# GB_Slave_2015.net
KiCad netlist of a schematic drawn in EAGLE
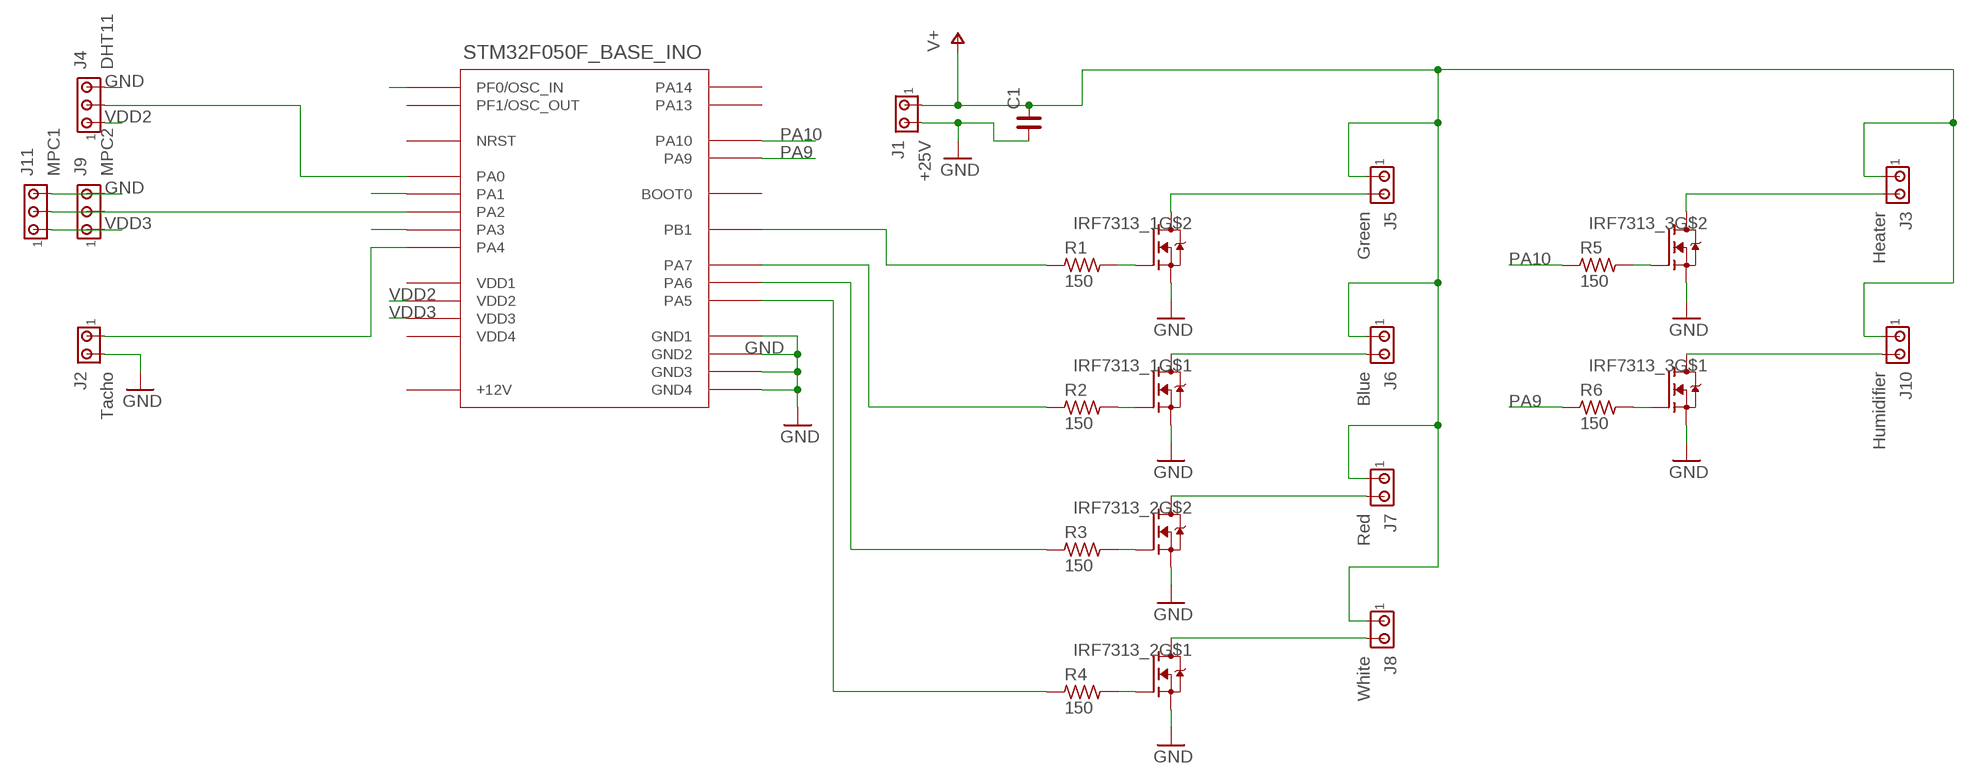
[diagram p0: schematic, sheet 1]

(export (version "E")
  (design (tool "Eeschema 10.0.6"))
  (components
    (comp (ref "C1")
      (value "C_0603")
      (footprint "eagle-import:C0603")
      (libsource (lib "eagle-import") (part "C_0603"))
    )
    (comp (ref "IRF7313_1")
      (value "IRF7313")
      (footprint "eagle-import:SO-8")
      (libsource (lib "eagle-import") (part "IRF7313"))
    )
    (comp (ref "IRF7313_2")
      (value "IRF7313")
      (footprint "eagle-import:SO-8")
      (libsource (lib "eagle-import") (part "IRF7313"))
    )
    (comp (ref "IRF7313_3")
      (value "IRF7313")
      (footprint "eagle-import:SO-8")
      (libsource (lib "eagle-import") (part "IRF7313"))
    )
    (comp (ref "J1")
      (value "+25V")
      (footprint "eagle-import:10X02MTA")
      (libsource (lib "eagle-import") (part "MTA02-100"))
    )
    (comp (ref "J2")
      (value "Tacho")
      (footprint "eagle-import:10X02MTA")
      (libsource (lib "eagle-import") (part "MTA02-100"))
    )
    (comp (ref "J3")
      (value "Heater")
      (footprint "eagle-import:10X02MTA")
      (libsource (lib "eagle-import") (part "MTA02-100"))
    )
    (comp (ref "J4")
      (value "DHT11")
      (footprint "eagle-import:10X03MTA")
      (libsource (lib "eagle-import") (part "MTA03-100"))
    )
    (comp (ref "J5")
      (value "Green")
      (footprint "eagle-import:10X02MTA")
      (libsource (lib "eagle-import") (part "MTA02-100"))
    )
    (comp (ref "J6")
      (value "Blue")
      (footprint "eagle-import:10X02MTA")
      (libsource (lib "eagle-import") (part "MTA02-100"))
    )
    (comp (ref "J7")
      (value "Red")
      (footprint "eagle-import:10X02MTA")
      (libsource (lib "eagle-import") (part "MTA02-100"))
    )
    (comp (ref "J8")
      (value "White")
      (footprint "eagle-import:10X02MTA")
      (libsource (lib "eagle-import") (part "MTA02-100"))
    )
    (comp (ref "J9")
      (value "MPC2")
      (footprint "eagle-import:10X03MTA")
      (libsource (lib "eagle-import") (part "MTA03-100"))
    )
    (comp (ref "J10")
      (value "Humidifier")
      (footprint "eagle-import:10X02MTA")
      (libsource (lib "eagle-import") (part "MTA02-100"))
    )
    (comp (ref "J11")
      (value "MPC1")
      (footprint "eagle-import:10X03MTA")
      (libsource (lib "eagle-import") (part "MTA03-100"))
    )
    (comp (ref "R1")
      (value "150")
      (footprint "eagle-import:R1206")
      (libsource (lib "eagle-import") (part "R_1206"))
    )
    (comp (ref "R2")
      (value "150")
      (footprint "eagle-import:R1206")
      (libsource (lib "eagle-import") (part "R_1206"))
    )
    (comp (ref "R3")
      (value "150")
      (footprint "eagle-import:R1206")
      (libsource (lib "eagle-import") (part "R_1206"))
    )
    (comp (ref "R4")
      (value "150")
      (footprint "eagle-import:R1206")
      (libsource (lib "eagle-import") (part "R_1206"))
    )
    (comp (ref "R5")
      (value "150")
      (footprint "eagle-import:R1206")
      (libsource (lib "eagle-import") (part "R_1206"))
    )
    (comp (ref "R6")
      (value "150")
      (footprint "eagle-import:R1206")
      (libsource (lib "eagle-import") (part "R_1206"))
    )
    (comp (ref "STM321")
      (value "STM32F050F_BASE_INO")
      (footprint "eagle-import:STM32_BASE_INO")
      (libsource (lib "eagle-import") (part "STM32F050F_BASE_INO"))
    )
  )
  (nets
    (net (code "1") (name "/PA9") (class "Default")
      (node (ref "R6") (pin "1") (pinfunction "1_1") (pintype "passive"))
      (node (ref "STM321") (pin "PA9") (pinfunction "PA9_PA9") (pintype "passive"))
    )
    (net (code "2") (name "/PA10") (class "Default")
      (node (ref "R5") (pin "1") (pinfunction "1_1") (pintype "passive"))
      (node (ref "STM321") (pin "PA10") (pinfunction "PA10_PA10") (pintype "passive"))
    )
    (net (code "3") (name "/VDD2") (class "Default")
      (node (ref "J4") (pin "1") (pinfunction "1_1") (pintype "passive"))
      (node (ref "STM321") (pin "VDD2") (pinfunction "VDD2_VDD2") (pintype "passive"))
    )
    (net (code "4") (name "/VDD3") (class "Default")
      (node (ref "J11") (pin "1") (pinfunction "1_1") (pintype "passive"))
      (node (ref "J9") (pin "1") (pinfunction "1_1") (pintype "passive"))
      (node (ref "STM321") (pin "VDD3") (pinfunction "VDD3_VDD3") (pintype "passive"))
    )
    (net (code "5") (name "GND") (class "Default")
      (node (ref "C1") (pin "1") (pinfunction "1_1") (pintype "passive"))
      (node (ref "IRF7313_1") (pin "1") (pinfunction "S_1") (pintype "passive"))
      (node (ref "IRF7313_1") (pin "3") (pinfunction "S_3") (pintype "passive"))
      (node (ref "IRF7313_2") (pin "1") (pinfunction "S_1") (pintype "passive"))
      (node (ref "IRF7313_2") (pin "3") (pinfunction "S_3") (pintype "passive"))
      (node (ref "IRF7313_3") (pin "1") (pinfunction "S_1") (pintype "passive"))
      (node (ref "IRF7313_3") (pin "3") (pinfunction "S_3") (pintype "passive"))
      (node (ref "J1") (pin "2") (pinfunction "2_2") (pintype "passive"))
      (node (ref "J11") (pin "3") (pinfunction "3_3") (pintype "passive"))
      (node (ref "J2") (pin "2") (pinfunction "2_2") (pintype "passive"))
      (node (ref "J4") (pin "3") (pinfunction "3_3") (pintype "passive"))
      (node (ref "J9") (pin "3") (pinfunction "3_3") (pintype "passive"))
      (node (ref "STM321") (pin "GND1") (pinfunction "GND1_GND1") (pintype "passive"))
      (node (ref "STM321") (pin "GND2") (pinfunction "GND2_GND2") (pintype "passive"))
      (node (ref "STM321") (pin "GND3") (pinfunction "GND3_GND3") (pintype "passive"))
      (node (ref "STM321") (pin "GND4") (pinfunction "GND4_GND4") (pintype "passive"))
    )
    (net (code "6") (name "Net-(IRF7313_1A-D-Pad7)") (class "Default")
      (node (ref "IRF7313_1") (pin "7") (pinfunction "D_7") (pintype "passive"))
      (node (ref "IRF7313_1") (pin "8") (pinfunction "D_8") (pintype "passive"))
      (node (ref "J6") (pin "2") (pinfunction "2_2") (pintype "passive"))
    )
    (net (code "7") (name "Net-(IRF7313_1A-G)") (class "Default")
      (node (ref "IRF7313_1") (pin "2") (pinfunction "G_2") (pintype "passive"))
      (node (ref "R2") (pin "2") (pinfunction "2_2") (pintype "passive"))
    )
    (net (code "8") (name "Net-(IRF7313_1B-D-Pad5)") (class "Default")
      (node (ref "IRF7313_1") (pin "5") (pinfunction "D_5") (pintype "passive"))
      (node (ref "IRF7313_1") (pin "6") (pinfunction "D_6") (pintype "passive"))
      (node (ref "J5") (pin "2") (pinfunction "2_2") (pintype "passive"))
    )
    (net (code "9") (name "Net-(IRF7313_1B-G)") (class "Default")
      (node (ref "IRF7313_1") (pin "4") (pinfunction "G_4") (pintype "passive"))
      (node (ref "R1") (pin "2") (pinfunction "2_2") (pintype "passive"))
    )
    (net (code "10") (name "Net-(IRF7313_2A-D-Pad7)") (class "Default")
      (node (ref "IRF7313_2") (pin "7") (pinfunction "D_7") (pintype "passive"))
      (node (ref "IRF7313_2") (pin "8") (pinfunction "D_8") (pintype "passive"))
      (node (ref "J8") (pin "2") (pinfunction "2_2") (pintype "passive"))
    )
    (net (code "11") (name "Net-(IRF7313_2A-G)") (class "Default")
      (node (ref "IRF7313_2") (pin "2") (pinfunction "G_2") (pintype "passive"))
      (node (ref "R4") (pin "2") (pinfunction "2_2") (pintype "passive"))
    )
    (net (code "12") (name "Net-(IRF7313_2B-D-Pad5)") (class "Default")
      (node (ref "IRF7313_2") (pin "5") (pinfunction "D_5") (pintype "passive"))
      (node (ref "IRF7313_2") (pin "6") (pinfunction "D_6") (pintype "passive"))
      (node (ref "J7") (pin "2") (pinfunction "2_2") (pintype "passive"))
    )
    (net (code "13") (name "Net-(IRF7313_2B-G)") (class "Default")
      (node (ref "IRF7313_2") (pin "4") (pinfunction "G_4") (pintype "passive"))
      (node (ref "R3") (pin "2") (pinfunction "2_2") (pintype "passive"))
    )
    (net (code "14") (name "Net-(IRF7313_3A-D-Pad7)") (class "Default")
      (node (ref "IRF7313_3") (pin "7") (pinfunction "D_7") (pintype "passive"))
      (node (ref "IRF7313_3") (pin "8") (pinfunction "D_8") (pintype "passive"))
      (node (ref "J10") (pin "2") (pinfunction "2_2") (pintype "passive"))
    )
    (net (code "15") (name "Net-(IRF7313_3A-G)") (class "Default")
      (node (ref "IRF7313_3") (pin "2") (pinfunction "G_2") (pintype "passive"))
      (node (ref "R6") (pin "2") (pinfunction "2_2") (pintype "passive"))
    )
    (net (code "16") (name "Net-(IRF7313_3B-D-Pad5)") (class "Default")
      (node (ref "IRF7313_3") (pin "5") (pinfunction "D_5") (pintype "passive"))
      (node (ref "IRF7313_3") (pin "6") (pinfunction "D_6") (pintype "passive"))
      (node (ref "J3") (pin "2") (pinfunction "2_2") (pintype "passive"))
    )
    (net (code "17") (name "Net-(IRF7313_3B-G)") (class "Default")
      (node (ref "IRF7313_3") (pin "4") (pinfunction "G_4") (pintype "passive"))
      (node (ref "R5") (pin "2") (pinfunction "2_2") (pintype "passive"))
    )
    (net (code "18") (name "Net-(J2-Pad1)") (class "Default")
      (node (ref "J2") (pin "1") (pinfunction "1_1") (pintype "passive"))
      (node (ref "STM321") (pin "PA4") (pinfunction "PA4_PA4") (pintype "passive"))
    )
    (net (code "19") (name "Net-(J4-Pad2)") (class "Default")
      (node (ref "J4") (pin "2") (pinfunction "2_2") (pintype "passive"))
      (node (ref "STM321") (pin "PA0") (pinfunction "PA0_PA0") (pintype "passive"))
    )
    (net (code "20") (name "Net-(J11-Pad2)") (class "Default")
      (node (ref "J11") (pin "2") (pinfunction "2_2") (pintype "passive"))
      (node (ref "J9") (pin "2") (pinfunction "2_2") (pintype "passive"))
      (node (ref "STM321") (pin "PA2") (pinfunction "PA2_PA2") (pintype "passive"))
    )
    (net (code "21") (name "Net-(R1-Pad1)") (class "Default")
      (node (ref "R1") (pin "1") (pinfunction "1_1") (pintype "passive"))
      (node (ref "STM321") (pin "PB1") (pinfunction "PB1_PB1") (pintype "passive"))
    )
    (net (code "22") (name "Net-(R2-Pad1)") (class "Default")
      (node (ref "R2") (pin "1") (pinfunction "1_1") (pintype "passive"))
      (node (ref "STM321") (pin "PA7") (pinfunction "PA7_PA7") (pintype "passive"))
    )
    (net (code "23") (name "Net-(R3-Pad1)") (class "Default")
      (node (ref "R3") (pin "1") (pinfunction "1_1") (pintype "passive"))
      (node (ref "STM321") (pin "PA6") (pinfunction "PA6_PA6") (pintype "passive"))
    )
    (net (code "24") (name "Net-(R4-Pad1)") (class "Default")
      (node (ref "R4") (pin "1") (pinfunction "1_1") (pintype "passive"))
      (node (ref "STM321") (pin "PA5") (pinfunction "PA5_PA5") (pintype "passive"))
    )
    (net (code "25") (name "V+") (class "Default")
      (node (ref "C1") (pin "2") (pinfunction "2_2") (pintype "passive"))
      (node (ref "J1") (pin "1") (pinfunction "1_1") (pintype "passive"))
      (node (ref "J10") (pin "1") (pinfunction "1_1") (pintype "passive"))
      (node (ref "J3") (pin "1") (pinfunction "1_1") (pintype "passive"))
      (node (ref "J5") (pin "1") (pinfunction "1_1") (pintype "passive"))
      (node (ref "J6") (pin "1") (pinfunction "1_1") (pintype "passive"))
      (node (ref "J7") (pin "1") (pinfunction "1_1") (pintype "passive"))
      (node (ref "J8") (pin "1") (pinfunction "1_1") (pintype "passive"))
    )
    (net (code "26") (name "unconnected-(STM321-PF0{slash}OSC_IN-PadPF0)") (class "Default")
      (node (ref "STM321") (pin "PF0") (pinfunction "PF0/OSC_IN_PF0") (pintype "passive"))
    )
    (net (code "27") (name "unconnected-(STM321-PF1{slash}OSC_OUT-PadPF1)") (class "Default")
      (node (ref "STM321") (pin "PF1") (pinfunction "PF1/OSC_OUT_PF1") (pintype "passive"))
    )
    (net (code "28") (name "unconnected-(STM321-Pad+12V)") (class "Default")
      (node (ref "STM321") (pin "+12V") (pinfunction "+12V_+12V") (pintype "passive"))
    )
    (net (code "29") (name "unconnected-(STM321-PadBOOT0)") (class "Default")
      (node (ref "STM321") (pin "BOOT0") (pinfunction "BOOT0_BOOT0") (pintype "passive"))
    )
    (net (code "30") (name "unconnected-(STM321-PadNRST)") (class "Default")
      (node (ref "STM321") (pin "NRST") (pinfunction "NRST_NRST") (pintype "passive"))
    )
    (net (code "31") (name "unconnected-(STM321-PadPA1)") (class "Default")
      (node (ref "STM321") (pin "PA1") (pinfunction "PA1_PA1") (pintype "passive"))
    )
    (net (code "32") (name "unconnected-(STM321-PadPA3)") (class "Default")
      (node (ref "STM321") (pin "PA3") (pinfunction "PA3_PA3") (pintype "passive"))
    )
    (net (code "33") (name "unconnected-(STM321-PadPA13)") (class "Default")
      (node (ref "STM321") (pin "PA13") (pinfunction "PA13_PA13") (pintype "passive"))
    )
    (net (code "34") (name "unconnected-(STM321-PadPA14)") (class "Default")
      (node (ref "STM321") (pin "PA14") (pinfunction "PA14_PA14") (pintype "passive"))
    )
    (net (code "35") (name "unconnected-(STM321-PadVDD1)") (class "Default")
      (node (ref "STM321") (pin "VDD1") (pinfunction "VDD1_VDD1") (pintype "passive"))
    )
    (net (code "36") (name "unconnected-(STM321-PadVDD4)") (class "Default")
      (node (ref "STM321") (pin "VDD4") (pinfunction "VDD4_VDD4") (pintype "passive"))
    )
  )
)
